# vco1_pots.net
KiCad netlist of a schematic drawn in EAGLE
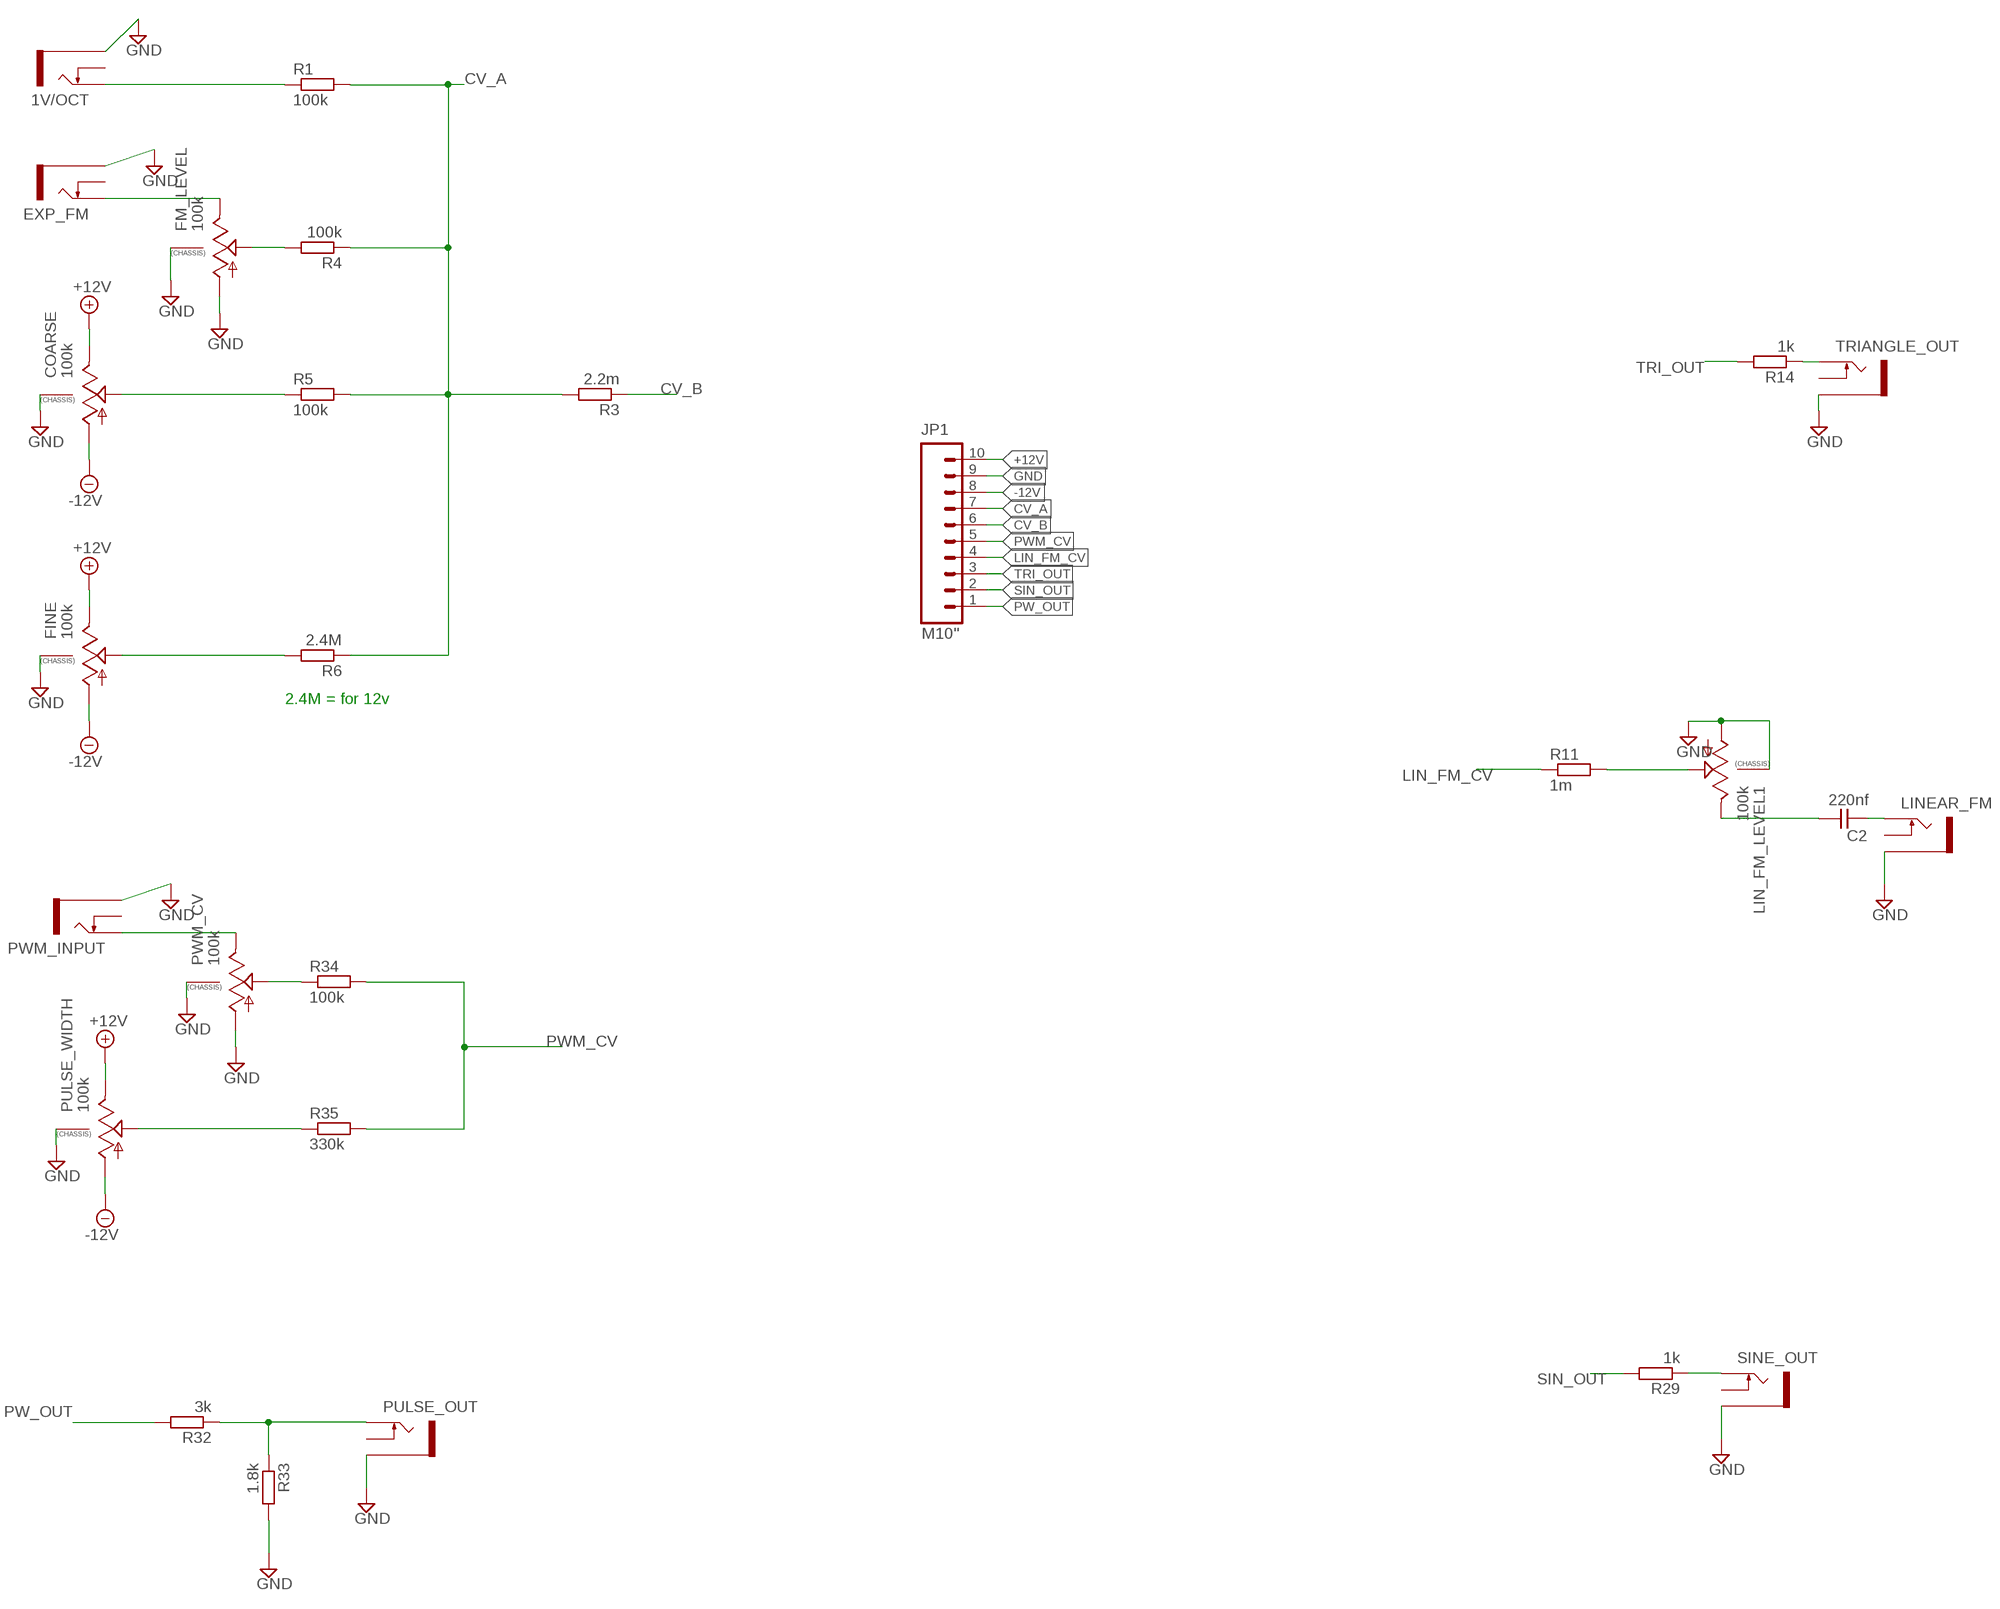
[diagram p0: schematic, sheet 1]

(export (version "E")
  (design (tool "Eeschema 10.0.6"))
  (components
    (comp (ref "1V/OCT")
      (value "THONKICONNNEW")
      (footprint "eagle-import:WQP-PJ301M-12_JACK")
      (libsource (lib "eagle-import") (part "THONKICONNNEW"))
    )
    (comp (ref "C2")
      (value "220nf")
      (footprint "eagle-import:C050-024X044")
      (libsource (lib "eagle-import") (part "C-EU050-024X044"))
    )
    (comp (ref "COARSE")
      (value "100k")
      (footprint "eagle-import:9MM_SNAP-IN_POT")
      (libsource (lib "eagle-import") (part "9MM_SNAP-IN_POT_CHASSIS"))
    )
    (comp (ref "EXP_FM")
      (value "THONKICONNNEW")
      (footprint "eagle-import:WQP-PJ301M-12_JACK")
      (libsource (lib "eagle-import") (part "THONKICONNNEW"))
    )
    (comp (ref "FINE")
      (value "100k")
      (footprint "eagle-import:9MM_SNAP-IN_POT")
      (libsource (lib "eagle-import") (part "9MM_SNAP-IN_POT_CHASSIS"))
    )
    (comp (ref "FM_LEVEL")
      (value "100k")
      (footprint "eagle-import:9MM_SNAP-IN_POT")
      (libsource (lib "eagle-import") (part "9MM_SNAP-IN_POT_CHASSIS"))
    )
    (comp (ref "JP1")
      (value "M10\"")
      (footprint "eagle-import:1X10")
      (libsource (lib "eagle-import") (part "M10{dblquote}"))
    )
    (comp (ref "LINEAR_FM")
      (value "THONKICONNNEW")
      (footprint "eagle-import:WQP-PJ301M-12_JACK")
      (libsource (lib "eagle-import") (part "THONKICONNNEW"))
    )
    (comp (ref "LIN_FM_LEVEL1")
      (value "100k")
      (footprint "eagle-import:9MM_SNAP-IN_POT")
      (libsource (lib "eagle-import") (part "9MM_SNAP-IN_POT_CHASSIS"))
    )
    (comp (ref "PULSE_OUT")
      (value "THONKICONNNEW")
      (footprint "eagle-import:WQP-PJ301M-12_JACK")
      (libsource (lib "eagle-import") (part "THONKICONNNEW"))
    )
    (comp (ref "PULSE_WIDTH")
      (value "100k")
      (footprint "eagle-import:9MM_SNAP-IN_POT")
      (libsource (lib "eagle-import") (part "9MM_SNAP-IN_POT_CHASSIS"))
    )
    (comp (ref "PWM_CV")
      (value "100k")
      (footprint "eagle-import:9MM_SNAP-IN_POT")
      (libsource (lib "eagle-import") (part "9MM_SNAP-IN_POT_CHASSIS"))
    )
    (comp (ref "PWM_INPUT")
      (value "THONKICONNNEW")
      (footprint "eagle-import:WQP-PJ301M-12_JACK")
      (libsource (lib "eagle-import") (part "THONKICONNNEW"))
    )
    (comp (ref "R1")
      (value "100k")
      (footprint "eagle-import:7MM_RESISTOR")
      (libsource (lib "eagle-import") (part "RESISTOR7MM"))
    )
    (comp (ref "R3")
      (value "2.2m")
      (footprint "eagle-import:7MM_RESISTOR")
      (libsource (lib "eagle-import") (part "RESISTOR7MM"))
    )
    (comp (ref "R4")
      (value "100k")
      (footprint "eagle-import:7MM_RESISTOR")
      (libsource (lib "eagle-import") (part "RESISTOR7MM"))
    )
    (comp (ref "R5")
      (value "100k")
      (footprint "eagle-import:7MM_RESISTOR")
      (libsource (lib "eagle-import") (part "RESISTOR7MM"))
    )
    (comp (ref "R6")
      (value "2.4M")
      (footprint "eagle-import:7MM_RESISTOR")
      (libsource (lib "eagle-import") (part "RESISTOR7MM"))
    )
    (comp (ref "R11")
      (value "1m")
      (footprint "eagle-import:7MM_RESISTOR")
      (libsource (lib "eagle-import") (part "RESISTOR7MM"))
    )
    (comp (ref "R14")
      (value "1k")
      (footprint "eagle-import:7MM_RESISTOR")
      (libsource (lib "eagle-import") (part "RESISTOR7MM"))
    )
    (comp (ref "R29")
      (value "1k")
      (footprint "eagle-import:7MM_RESISTOR")
      (libsource (lib "eagle-import") (part "RESISTOR7MM"))
    )
    (comp (ref "R32")
      (value "3k")
      (footprint "eagle-import:7MM_RESISTOR")
      (libsource (lib "eagle-import") (part "RESISTOR7MM"))
    )
    (comp (ref "R33")
      (value "1.8k")
      (footprint "eagle-import:7MM_RESISTOR")
      (libsource (lib "eagle-import") (part "RESISTOR7MM"))
    )
    (comp (ref "R34")
      (value "100k")
      (footprint "eagle-import:7MM_RESISTOR")
      (libsource (lib "eagle-import") (part "RESISTOR7MM"))
    )
    (comp (ref "R35")
      (value "330k")
      (footprint "eagle-import:7MM_RESISTOR")
      (libsource (lib "eagle-import") (part "RESISTOR7MM"))
    )
    (comp (ref "SINE_OUT")
      (value "THONKICONNNEW")
      (footprint "eagle-import:WQP-PJ301M-12_JACK")
      (libsource (lib "eagle-import") (part "THONKICONNNEW"))
    )
    (comp (ref "TRIANGLE_OUT")
      (value "THONKICONNNEW")
      (footprint "eagle-import:WQP-PJ301M-12_JACK")
      (libsource (lib "eagle-import") (part "THONKICONNNEW"))
    )
  )
  (nets
    (net (code "1") (name "+12V") (class "Default")
      (node (ref "COARSE") (pin "3") (pinfunction "E_3") (pintype "passive"))
      (node (ref "FINE") (pin "3") (pinfunction "E_3") (pintype "passive"))
      (node (ref "JP1") (pin "10") (pinfunction "10_10") (pintype "passive"))
      (node (ref "PULSE_WIDTH") (pin "3") (pinfunction "E_3") (pintype "passive"))
    )
    (net (code "2") (name "-12V") (class "Default")
      (node (ref "COARSE") (pin "1") (pinfunction "A_1") (pintype "passive"))
      (node (ref "FINE") (pin "1") (pinfunction "A_1") (pintype "passive"))
      (node (ref "JP1") (pin "8") (pinfunction "8_8") (pintype "passive"))
      (node (ref "PULSE_WIDTH") (pin "1") (pinfunction "A_1") (pintype "passive"))
    )
    (net (code "3") (name "CV_A") (class "Default")
      (node (ref "JP1") (pin "7") (pinfunction "7_7") (pintype "passive"))
      (node (ref "R1") (pin "2") (pinfunction "2_2") (pintype "passive"))
      (node (ref "R3") (pin "2") (pinfunction "2_2") (pintype "passive"))
      (node (ref "R4") (pin "1") (pinfunction "1_1") (pintype "passive"))
      (node (ref "R5") (pin "2") (pinfunction "2_2") (pintype "passive"))
      (node (ref "R6") (pin "1") (pinfunction "1_1") (pintype "passive"))
    )
    (net (code "4") (name "CV_B") (class "Default")
      (node (ref "JP1") (pin "6") (pinfunction "6_6") (pintype "passive"))
      (node (ref "R3") (pin "1") (pinfunction "1_1") (pintype "passive"))
    )
    (net (code "5") (name "GND") (class "Default")
      (node (ref "1V/OCT") (pin "P$3_SLEEVE") (pinfunction "SLEEVE_P$3_SLEEVE") (pintype "passive"))
      (node (ref "COARSE") (pin "CHASSIS2") (pinfunction "P$1_CHASSIS2") (pintype "passive"))
      (node (ref "EXP_FM") (pin "P$3_SLEEVE") (pinfunction "SLEEVE_P$3_SLEEVE") (pintype "passive"))
      (node (ref "FINE") (pin "CHASSIS2") (pinfunction "P$1_CHASSIS2") (pintype "passive"))
      (node (ref "FM_LEVEL") (pin "1") (pinfunction "A_1") (pintype "passive"))
      (node (ref "FM_LEVEL") (pin "CHASSIS2") (pinfunction "P$1_CHASSIS2") (pintype "passive"))
      (node (ref "JP1") (pin "9") (pinfunction "9_9") (pintype "passive"))
      (node (ref "LINEAR_FM") (pin "P$3_SLEEVE") (pinfunction "SLEEVE_P$3_SLEEVE") (pintype "passive"))
      (node (ref "LIN_FM_LEVEL1") (pin "1") (pinfunction "A_1") (pintype "passive"))
      (node (ref "LIN_FM_LEVEL1") (pin "CHASSIS2") (pinfunction "P$1_CHASSIS2") (pintype "passive"))
      (node (ref "PULSE_OUT") (pin "P$3_SLEEVE") (pinfunction "SLEEVE_P$3_SLEEVE") (pintype "passive"))
      (node (ref "PULSE_WIDTH") (pin "CHASSIS2") (pinfunction "P$1_CHASSIS2") (pintype "passive"))
      (node (ref "PWM_CV") (pin "1") (pinfunction "A_1") (pintype "passive"))
      (node (ref "PWM_CV") (pin "CHASSIS2") (pinfunction "P$1_CHASSIS2") (pintype "passive"))
      (node (ref "PWM_INPUT") (pin "P$3_SLEEVE") (pinfunction "SLEEVE_P$3_SLEEVE") (pintype "passive"))
      (node (ref "R33") (pin "2") (pinfunction "2_2") (pintype "passive"))
      (node (ref "SINE_OUT") (pin "P$3_SLEEVE") (pinfunction "SLEEVE_P$3_SLEEVE") (pintype "passive"))
      (node (ref "TRIANGLE_OUT") (pin "P$3_SLEEVE") (pinfunction "SLEEVE_P$3_SLEEVE") (pintype "passive"))
    )
    (net (code "6") (name "LIN_FM_CV") (class "Default")
      (node (ref "JP1") (pin "4") (pinfunction "4_4") (pintype "passive"))
      (node (ref "R11") (pin "1") (pinfunction "1_1") (pintype "passive"))
    )
    (net (code "7") (name "Net-(1V/OCT-TIP)") (class "Default")
      (node (ref "1V/OCT") (pin "P$1_TIP") (pinfunction "TIP_P$1_TIP") (pintype "passive"))
      (node (ref "R1") (pin "1") (pinfunction "1_1") (pintype "passive"))
    )
    (net (code "8") (name "Net-(COARSE-S)") (class "Default")
      (node (ref "COARSE") (pin "2") (pinfunction "S_2") (pintype "passive"))
      (node (ref "R5") (pin "1") (pinfunction "1_1") (pintype "passive"))
    )
    (net (code "9") (name "Net-(EXP_FM-TIP)") (class "Default")
      (node (ref "EXP_FM") (pin "P$1_TIP") (pinfunction "TIP_P$1_TIP") (pintype "passive"))
      (node (ref "FM_LEVEL") (pin "3") (pinfunction "E_3") (pintype "passive"))
    )
    (net (code "10") (name "Net-(FINE-S)") (class "Default")
      (node (ref "FINE") (pin "2") (pinfunction "S_2") (pintype "passive"))
      (node (ref "R6") (pin "2") (pinfunction "2_2") (pintype "passive"))
    )
    (net (code "11") (name "Net-(FM_LEVEL-S)") (class "Default")
      (node (ref "FM_LEVEL") (pin "2") (pinfunction "S_2") (pintype "passive"))
      (node (ref "R4") (pin "2") (pinfunction "2_2") (pintype "passive"))
    )
    (net (code "12") (name "Net-(LINEAR_FM-TIP)") (class "Default")
      (node (ref "C2") (pin "2") (pinfunction "2_2") (pintype "passive"))
      (node (ref "LINEAR_FM") (pin "P$1_TIP") (pinfunction "TIP_P$1_TIP") (pintype "passive"))
    )
    (net (code "13") (name "Net-(LIN_FM_LEVEL1-E)") (class "Default")
      (node (ref "C2") (pin "1") (pinfunction "1_1") (pintype "passive"))
      (node (ref "LIN_FM_LEVEL1") (pin "3") (pinfunction "E_3") (pintype "passive"))
    )
    (net (code "14") (name "Net-(LIN_FM_LEVEL1-S)") (class "Default")
      (node (ref "LIN_FM_LEVEL1") (pin "2") (pinfunction "S_2") (pintype "passive"))
      (node (ref "R11") (pin "2") (pinfunction "2_2") (pintype "passive"))
    )
    (net (code "15") (name "Net-(PULSE_OUT-TIP)") (class "Default")
      (node (ref "PULSE_OUT") (pin "P$1_TIP") (pinfunction "TIP_P$1_TIP") (pintype "passive"))
      (node (ref "R32") (pin "1") (pinfunction "1_1") (pintype "passive"))
      (node (ref "R33") (pin "1") (pinfunction "1_1") (pintype "passive"))
    )
    (net (code "16") (name "Net-(PULSE_WIDTH-S)") (class "Default")
      (node (ref "PULSE_WIDTH") (pin "2") (pinfunction "S_2") (pintype "passive"))
      (node (ref "R35") (pin "1") (pinfunction "1_1") (pintype "passive"))
    )
    (net (code "17") (name "Net-(PWM_CV-E)") (class "Default")
      (node (ref "PWM_CV") (pin "3") (pinfunction "E_3") (pintype "passive"))
      (node (ref "PWM_INPUT") (pin "P$1_TIP") (pinfunction "TIP_P$1_TIP") (pintype "passive"))
    )
    (net (code "18") (name "Net-(PWM_CV-S)") (class "Default")
      (node (ref "PWM_CV") (pin "2") (pinfunction "S_2") (pintype "passive"))
      (node (ref "R34") (pin "1") (pinfunction "1_1") (pintype "passive"))
    )
    (net (code "19") (name "Net-(SINE_OUT-TIP)") (class "Default")
      (node (ref "R29") (pin "1") (pinfunction "1_1") (pintype "passive"))
      (node (ref "SINE_OUT") (pin "P$1_TIP") (pinfunction "TIP_P$1_TIP") (pintype "passive"))
    )
    (net (code "20") (name "Net-(TRIANGLE_OUT-TIP)") (class "Default")
      (node (ref "R14") (pin "1") (pinfunction "1_1") (pintype "passive"))
      (node (ref "TRIANGLE_OUT") (pin "P$1_TIP") (pinfunction "TIP_P$1_TIP") (pintype "passive"))
    )
    (net (code "21") (name "PWM_CV") (class "Default")
      (node (ref "JP1") (pin "5") (pinfunction "5_5") (pintype "passive"))
      (node (ref "R34") (pin "2") (pinfunction "2_2") (pintype "passive"))
      (node (ref "R35") (pin "2") (pinfunction "2_2") (pintype "passive"))
    )
    (net (code "22") (name "PW_OUT") (class "Default")
      (node (ref "JP1") (pin "1") (pinfunction "1_1") (pintype "passive"))
      (node (ref "R32") (pin "2") (pinfunction "2_2") (pintype "passive"))
    )
    (net (code "23") (name "SIN_OUT") (class "Default")
      (node (ref "JP1") (pin "2") (pinfunction "2_2") (pintype "passive"))
      (node (ref "R29") (pin "2") (pinfunction "2_2") (pintype "passive"))
    )
    (net (code "24") (name "TRI_OUT") (class "Default")
      (node (ref "JP1") (pin "3") (pinfunction "3_3") (pintype "passive"))
      (node (ref "R14") (pin "2") (pinfunction "2_2") (pintype "passive"))
    )
    (net (code "25") (name "unconnected-(1V/OCT-SWITCH-PadP$2_SWITCH)") (class "Default")
      (node (ref "1V/OCT") (pin "P$2_SWITCH") (pinfunction "SWITCH_P$2_SWITCH") (pintype "passive"))
    )
    (net (code "26") (name "unconnected-(EXP_FM-SWITCH-PadP$2_SWITCH)") (class "Default")
      (node (ref "EXP_FM") (pin "P$2_SWITCH") (pinfunction "SWITCH_P$2_SWITCH") (pintype "passive"))
    )
    (net (code "27") (name "unconnected-(LINEAR_FM-SWITCH-PadP$2_SWITCH)") (class "Default")
      (node (ref "LINEAR_FM") (pin "P$2_SWITCH") (pinfunction "SWITCH_P$2_SWITCH") (pintype "passive"))
    )
    (net (code "28") (name "unconnected-(PULSE_OUT-SWITCH-PadP$2_SWITCH)") (class "Default")
      (node (ref "PULSE_OUT") (pin "P$2_SWITCH") (pinfunction "SWITCH_P$2_SWITCH") (pintype "passive"))
    )
    (net (code "29") (name "unconnected-(PWM_INPUT-SWITCH-PadP$2_SWITCH)") (class "Default")
      (node (ref "PWM_INPUT") (pin "P$2_SWITCH") (pinfunction "SWITCH_P$2_SWITCH") (pintype "passive"))
    )
    (net (code "30") (name "unconnected-(SINE_OUT-SWITCH-PadP$2_SWITCH)") (class "Default")
      (node (ref "SINE_OUT") (pin "P$2_SWITCH") (pinfunction "SWITCH_P$2_SWITCH") (pintype "passive"))
    )
    (net (code "31") (name "unconnected-(TRIANGLE_OUT-SWITCH-PadP$2_SWITCH)") (class "Default")
      (node (ref "TRIANGLE_OUT") (pin "P$2_SWITCH") (pinfunction "SWITCH_P$2_SWITCH") (pintype "passive"))
    )
  )
)
